# WaterThePlants168.net
KiCad netlist of a schematic drawn in EAGLE
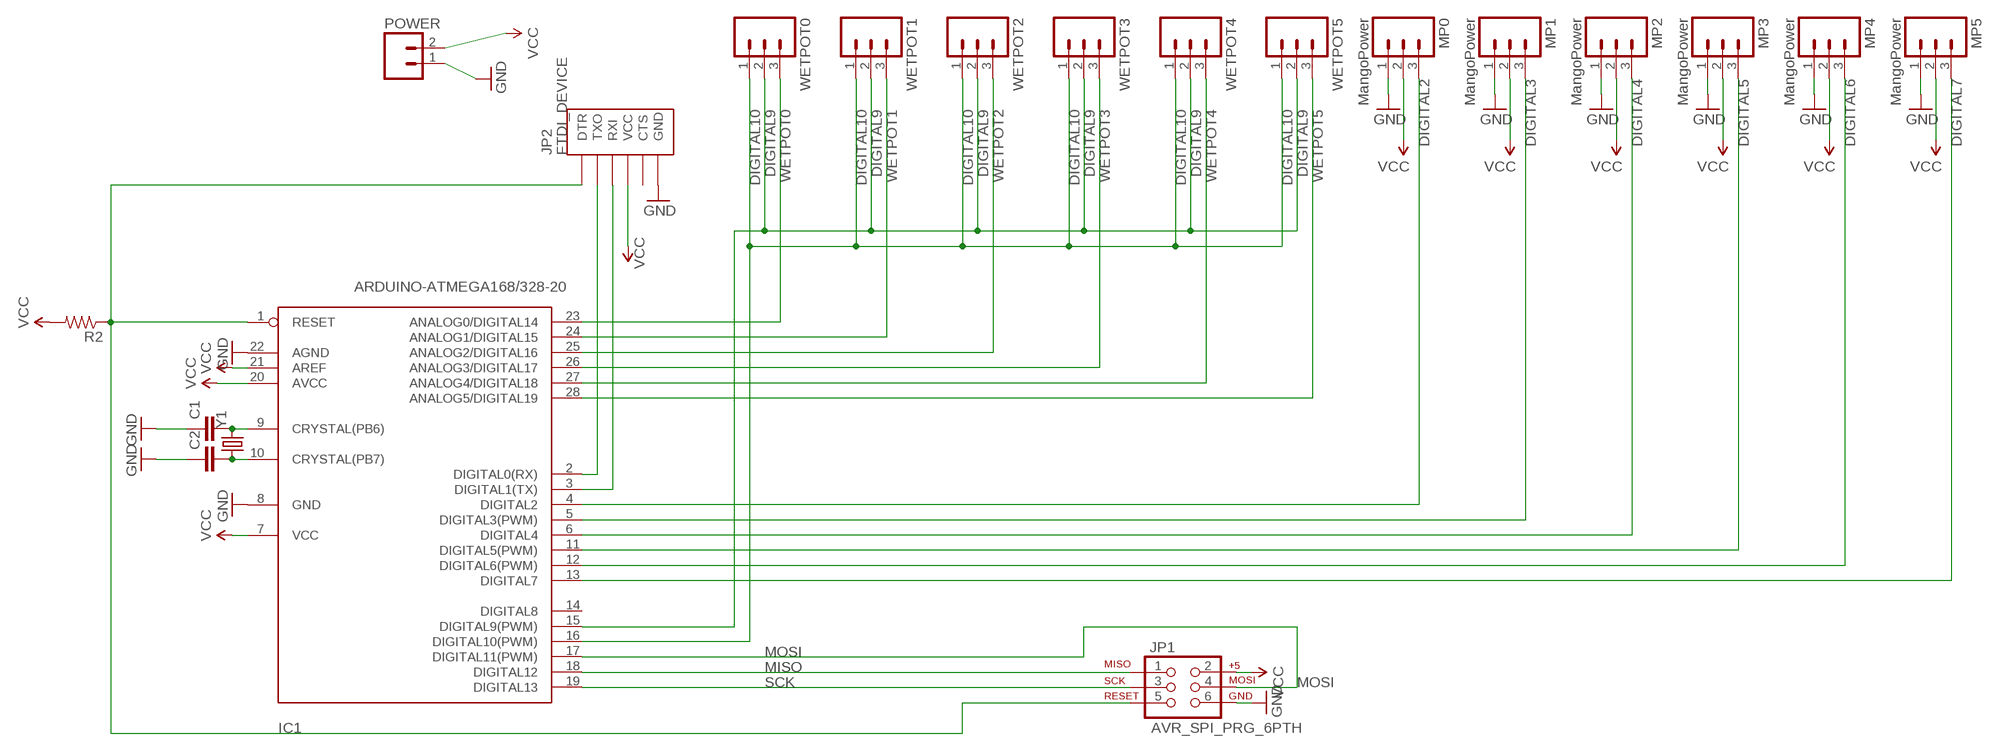
[diagram p0: schematic, sheet 1]

(export (version "E")
  (design (tool "Eeschema 10.0.6"))
  (components
    (comp (ref "C1")
      (value "CAPPTH2")
      (footprint "eagle-import:CAP-PTH-SMALL2")
      (libsource (lib "eagle-import") (part "CAPPTH2"))
    )
    (comp (ref "C2")
      (value "CAPPTH2")
      (footprint "eagle-import:CAP-PTH-SMALL2")
      (libsource (lib "eagle-import") (part "CAPPTH2"))
    )
    (comp (ref "IC1")
      (value "ARDUINO-ATMEGA168/328-20")
      (footprint "eagle-import:DIL28-3")
      (libsource (lib "eagle-import") (part "ARDUINO-ATMEGA168/328-20"))
    )
    (comp (ref "JP1")
      (value "AVR_SPI_PRG_6PTH")
      (footprint "eagle-import:2X3")
      (libsource (lib "eagle-import") (part "AVR_SPI_PRG_6PTH"))
    )
    (comp (ref "JP2")
      (value "FTDI_DEVICE")
      (footprint "eagle-import:FTDI_DEVICE_SIDE")
      (libsource (lib "eagle-import") (part "FTDI_DEVICE"))
    )
    (comp (ref "MP0")
      (value "MangoPower")
      (footprint "eagle-import:1X03")
      (libsource (lib "eagle-import") (part "M03PTH"))
    )
    (comp (ref "MP1")
      (value "MangoPower")
      (footprint "eagle-import:1X03")
      (libsource (lib "eagle-import") (part "M03PTH"))
    )
    (comp (ref "MP2")
      (value "MangoPower")
      (footprint "eagle-import:1X03")
      (libsource (lib "eagle-import") (part "M03PTH"))
    )
    (comp (ref "MP3")
      (value "MangoPower")
      (footprint "eagle-import:1X03")
      (libsource (lib "eagle-import") (part "M03PTH"))
    )
    (comp (ref "MP4")
      (value "MangoPower")
      (footprint "eagle-import:1X03")
      (libsource (lib "eagle-import") (part "M03PTH"))
    )
    (comp (ref "MP5")
      (value "MangoPower")
      (footprint "eagle-import:1X03")
      (libsource (lib "eagle-import") (part "M03PTH"))
    )
    (comp (ref "POWER")
      (value "M02POLAR")
      (footprint "eagle-import:MOLEX-1X2")
      (libsource (lib "eagle-import") (part "M02POLAR"))
    )
    (comp (ref "R2")
      (value "RESISTORAXIAL-0.3")
      (footprint "eagle-import:AXIAL-0.3")
      (libsource (lib "eagle-import") (part "RESISTORAXIAL-0.3"))
    )
    (comp (ref "WETPOT0")
      (value "M03PTH")
      (footprint "eagle-import:1X03")
      (libsource (lib "eagle-import") (part "M03PTH"))
    )
    (comp (ref "WETPOT1")
      (value "M03PTH")
      (footprint "eagle-import:1X03")
      (libsource (lib "eagle-import") (part "M03PTH"))
    )
    (comp (ref "WETPOT2")
      (value "M03PTH")
      (footprint "eagle-import:1X03")
      (libsource (lib "eagle-import") (part "M03PTH"))
    )
    (comp (ref "WETPOT3")
      (value "M03PTH")
      (footprint "eagle-import:1X03")
      (libsource (lib "eagle-import") (part "M03PTH"))
    )
    (comp (ref "WETPOT4")
      (value "M03PTH")
      (footprint "eagle-import:1X03")
      (libsource (lib "eagle-import") (part "M03PTH"))
    )
    (comp (ref "WETPOT5")
      (value "M03PTH")
      (footprint "eagle-import:1X03")
      (libsource (lib "eagle-import") (part "M03PTH"))
    )
    (comp (ref "Y1")
      (value "CRYSTALHC49US")
      (footprint "eagle-import:HC49US")
      (libsource (lib "eagle-import") (part "CRYSTALHC49US"))
    )
  )
  (nets
    (net (code "1") (name "/DIGITAL2") (class "Default")
      (node (ref "IC1") (pin "4") (pinfunction "DIGITAL2_4") (pintype "bidirectional"))
      (node (ref "MP0") (pin "3") (pinfunction "3_3") (pintype "passive"))
    )
    (net (code "2") (name "/DIGITAL3") (class "Default")
      (node (ref "IC1") (pin "5") (pinfunction "DIGITAL3(PWM)_5") (pintype "bidirectional"))
      (node (ref "MP1") (pin "3") (pinfunction "3_3") (pintype "passive"))
    )
    (net (code "3") (name "/DIGITAL4") (class "Default")
      (node (ref "IC1") (pin "6") (pinfunction "DIGITAL4_6") (pintype "bidirectional"))
      (node (ref "MP2") (pin "3") (pinfunction "3_3") (pintype "passive"))
    )
    (net (code "4") (name "/DIGITAL5") (class "Default")
      (node (ref "IC1") (pin "11") (pinfunction "DIGITAL5(PWM)_11") (pintype "bidirectional"))
      (node (ref "MP3") (pin "3") (pinfunction "3_3") (pintype "passive"))
    )
    (net (code "5") (name "/DIGITAL6") (class "Default")
      (node (ref "IC1") (pin "12") (pinfunction "DIGITAL6(PWM)_12") (pintype "bidirectional"))
      (node (ref "MP4") (pin "3") (pinfunction "3_3") (pintype "passive"))
    )
    (net (code "6") (name "/DIGITAL7") (class "Default")
      (node (ref "IC1") (pin "13") (pinfunction "DIGITAL7_13") (pintype "bidirectional"))
      (node (ref "MP5") (pin "3") (pinfunction "3_3") (pintype "passive"))
    )
    (net (code "7") (name "/DIGITAL9") (class "Default")
      (node (ref "IC1") (pin "15") (pinfunction "DIGITAL9(PWM)_15") (pintype "bidirectional"))
      (node (ref "WETPOT0") (pin "2") (pinfunction "2_2") (pintype "passive"))
      (node (ref "WETPOT1") (pin "2") (pinfunction "2_2") (pintype "passive"))
      (node (ref "WETPOT2") (pin "2") (pinfunction "2_2") (pintype "passive"))
      (node (ref "WETPOT3") (pin "2") (pinfunction "2_2") (pintype "passive"))
      (node (ref "WETPOT4") (pin "2") (pinfunction "2_2") (pintype "passive"))
      (node (ref "WETPOT5") (pin "2") (pinfunction "2_2") (pintype "passive"))
    )
    (net (code "8") (name "/DIGITAL10") (class "Default")
      (node (ref "IC1") (pin "16") (pinfunction "DIGITAL10(PWM)_16") (pintype "bidirectional"))
      (node (ref "WETPOT0") (pin "1") (pinfunction "1_1") (pintype "passive"))
      (node (ref "WETPOT1") (pin "1") (pinfunction "1_1") (pintype "passive"))
      (node (ref "WETPOT2") (pin "1") (pinfunction "1_1") (pintype "passive"))
      (node (ref "WETPOT3") (pin "1") (pinfunction "1_1") (pintype "passive"))
      (node (ref "WETPOT4") (pin "1") (pinfunction "1_1") (pintype "passive"))
      (node (ref "WETPOT5") (pin "1") (pinfunction "1_1") (pintype "passive"))
    )
    (net (code "9") (name "/MISO") (class "Default")
      (node (ref "IC1") (pin "18") (pinfunction "DIGITAL12_18") (pintype "bidirectional"))
      (node (ref "JP1") (pin "1") (pinfunction "1_1") (pintype "passive"))
    )
    (net (code "10") (name "/MOSI") (class "Default")
      (node (ref "IC1") (pin "17") (pinfunction "DIGITAL11(PWM)_17") (pintype "bidirectional"))
      (node (ref "JP1") (pin "4") (pinfunction "4_4") (pintype "passive"))
    )
    (net (code "11") (name "/SCK") (class "Default")
      (node (ref "IC1") (pin "19") (pinfunction "DIGITAL13_19") (pintype "bidirectional"))
      (node (ref "JP1") (pin "3") (pinfunction "3_3") (pintype "passive"))
    )
    (net (code "12") (name "/WETPOT0") (class "Default")
      (node (ref "IC1") (pin "23") (pinfunction "ANALOG0/DIGITAL14_23") (pintype "bidirectional"))
      (node (ref "WETPOT0") (pin "3") (pinfunction "3_3") (pintype "passive"))
    )
    (net (code "13") (name "/WETPOT1") (class "Default")
      (node (ref "IC1") (pin "24") (pinfunction "ANALOG1/DIGITAL15_24") (pintype "bidirectional"))
      (node (ref "WETPOT1") (pin "3") (pinfunction "3_3") (pintype "passive"))
    )
    (net (code "14") (name "/WETPOT2") (class "Default")
      (node (ref "IC1") (pin "25") (pinfunction "ANALOG2/DIGITAL16_25") (pintype "bidirectional"))
      (node (ref "WETPOT2") (pin "3") (pinfunction "3_3") (pintype "passive"))
    )
    (net (code "15") (name "/WETPOT3") (class "Default")
      (node (ref "IC1") (pin "26") (pinfunction "ANALOG3/DIGITAL17_26") (pintype "bidirectional"))
      (node (ref "WETPOT3") (pin "3") (pinfunction "3_3") (pintype "passive"))
    )
    (net (code "16") (name "/WETPOT4") (class "Default")
      (node (ref "IC1") (pin "27") (pinfunction "ANALOG4/DIGITAL18_27") (pintype "bidirectional"))
      (node (ref "WETPOT4") (pin "3") (pinfunction "3_3") (pintype "passive"))
    )
    (net (code "17") (name "/WETPOT5") (class "Default")
      (node (ref "IC1") (pin "28") (pinfunction "ANALOG5/DIGITAL19_28") (pintype "bidirectional"))
      (node (ref "WETPOT5") (pin "3") (pinfunction "3_3") (pintype "passive"))
    )
    (net (code "18") (name "GND") (class "Default")
      (node (ref "C1") (pin "1") (pinfunction "1_1") (pintype "passive"))
      (node (ref "C2") (pin "1") (pinfunction "1_1") (pintype "passive"))
      (node (ref "IC1") (pin "22") (pinfunction "AGND_22") (pintype "bidirectional"))
      (node (ref "IC1") (pin "8") (pinfunction "GND_8") (pintype "bidirectional"))
      (node (ref "JP1") (pin "6") (pinfunction "6_6") (pintype "passive"))
      (node (ref "JP2") (pin "P$6") (pinfunction "GND_P$6") (pintype "bidirectional"))
      (node (ref "MP0") (pin "1") (pinfunction "1_1") (pintype "passive"))
      (node (ref "MP1") (pin "1") (pinfunction "1_1") (pintype "passive"))
      (node (ref "MP2") (pin "1") (pinfunction "1_1") (pintype "passive"))
      (node (ref "MP3") (pin "1") (pinfunction "1_1") (pintype "passive"))
      (node (ref "MP4") (pin "1") (pinfunction "1_1") (pintype "passive"))
      (node (ref "MP5") (pin "1") (pinfunction "1_1") (pintype "passive"))
      (node (ref "POWER") (pin "1") (pinfunction "1_1") (pintype "passive"))
    )
    (net (code "19") (name "Net-(IC1-CRYSTAL(PB6))") (class "Default")
      (node (ref "C1") (pin "2") (pinfunction "2_2") (pintype "passive"))
      (node (ref "IC1") (pin "9") (pinfunction "CRYSTAL(PB6)_9") (pintype "bidirectional"))
      (node (ref "Y1") (pin "2") (pinfunction "2_2") (pintype "passive"))
    )
    (net (code "20") (name "Net-(IC1-CRYSTAL(PB7))") (class "Default")
      (node (ref "C2") (pin "2") (pinfunction "2_2") (pintype "passive"))
      (node (ref "IC1") (pin "10") (pinfunction "CRYSTAL(PB7)_10") (pintype "bidirectional"))
      (node (ref "Y1") (pin "1") (pinfunction "1_1") (pintype "passive"))
    )
    (net (code "21") (name "Net-(IC1-DIGITAL0(RX))") (class "Default")
      (node (ref "IC1") (pin "2") (pinfunction "DIGITAL0(RX)_2") (pintype "bidirectional"))
      (node (ref "JP2") (pin "P$2") (pinfunction "TXO_P$2") (pintype "bidirectional"))
    )
    (net (code "22") (name "Net-(IC1-DIGITAL1(TX))") (class "Default")
      (node (ref "IC1") (pin "3") (pinfunction "DIGITAL1(TX)_3") (pintype "bidirectional"))
      (node (ref "JP2") (pin "P$3") (pinfunction "RXI_P$3") (pintype "bidirectional"))
    )
    (net (code "23") (name "Net-(IC1-RESET)") (class "Default")
      (node (ref "IC1") (pin "1") (pinfunction "RESET_1") (pintype "bidirectional"))
      (node (ref "JP1") (pin "5") (pinfunction "5_5") (pintype "passive"))
      (node (ref "JP2") (pin "P$1") (pinfunction "DTR_P$1") (pintype "bidirectional"))
      (node (ref "R2") (pin "P$1") (pinfunction "1_P$1") (pintype "passive"))
    )
    (net (code "24") (name "VCC") (class "Default")
      (node (ref "IC1") (pin "20") (pinfunction "AVCC_20") (pintype "bidirectional"))
      (node (ref "IC1") (pin "21") (pinfunction "AREF_21") (pintype "bidirectional"))
      (node (ref "IC1") (pin "7") (pinfunction "VCC_7") (pintype "bidirectional"))
      (node (ref "JP1") (pin "2") (pinfunction "2_2") (pintype "passive"))
      (node (ref "JP2") (pin "P$4") (pinfunction "VCC_P$4") (pintype "bidirectional"))
      (node (ref "MP0") (pin "2") (pinfunction "2_2") (pintype "passive"))
      (node (ref "MP1") (pin "2") (pinfunction "2_2") (pintype "passive"))
      (node (ref "MP2") (pin "2") (pinfunction "2_2") (pintype "passive"))
      (node (ref "MP3") (pin "2") (pinfunction "2_2") (pintype "passive"))
      (node (ref "MP4") (pin "2") (pinfunction "2_2") (pintype "passive"))
      (node (ref "MP5") (pin "2") (pinfunction "2_2") (pintype "passive"))
      (node (ref "POWER") (pin "2") (pinfunction "2_2") (pintype "passive"))
      (node (ref "R2") (pin "P$2") (pinfunction "2_P$2") (pintype "passive"))
    )
    (net (code "25") (name "unconnected-(IC1-DIGITAL8-Pad14)") (class "Default")
      (node (ref "IC1") (pin "14") (pinfunction "DIGITAL8_14") (pintype "bidirectional"))
    )
    (net (code "26") (name "unconnected-(JP2-CTS-PadP$5)") (class "Default")
      (node (ref "JP2") (pin "P$5") (pinfunction "CTS_P$5") (pintype "bidirectional"))
    )
  )
)
